# rev18.net
KiCad netlist of a schematic drawn in EAGLE
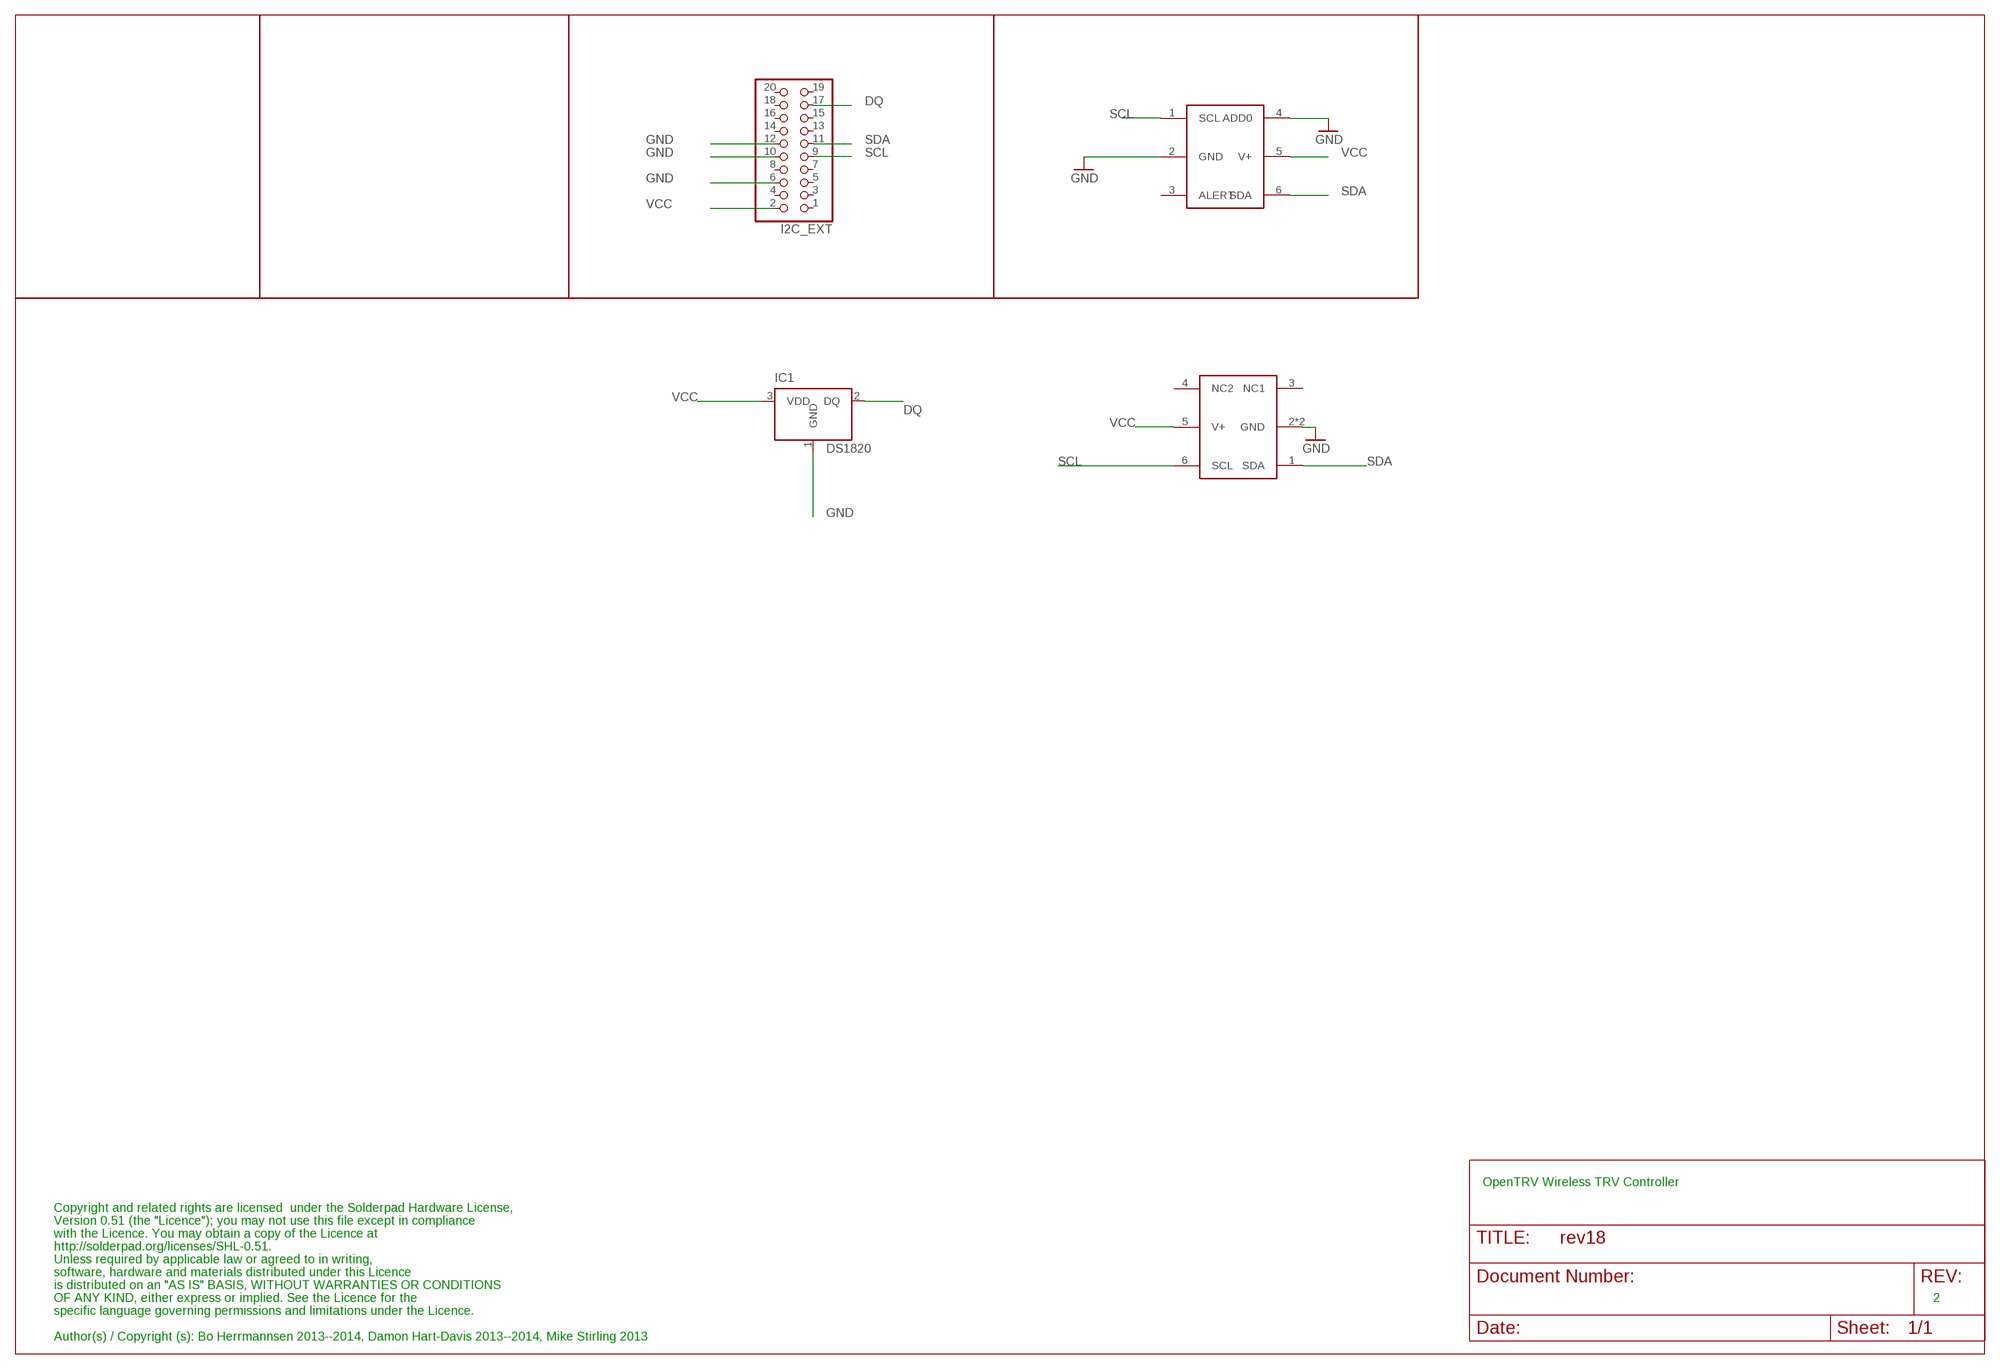
[diagram p0: schematic, sheet 1]

(export (version "E")
  (design (tool "Eeschema 10.0.6"))
  (components
    (comp (ref "I2C_EXT")
      (value "PINHD-2X10")
      (footprint "eagle-import:2X10")
      (libsource (lib "eagle-import") (part "PINHD-2X10"))
    )
    (comp (ref "IC1")
      (value "DS1820")
      (footprint "eagle-import:TO-92")
      (libsource (lib "eagle-import") (part "DS1820"))
    )
    (comp (ref "TMP112")
      (value "TMP1")
      (footprint "eagle-import:TMP112")
      (libsource (lib "eagle-import") (part "TMP112"))
    )
    (comp (ref "U$4")
      (value "SHT21")
      (footprint "eagle-import:SHT21")
      (libsource (lib "eagle-import") (part "SHT21"))
    )
  )
  (nets
    (net (code "1") (name "/DQ") (class "Default")
      (node (ref "I2C_EXT") (pin "17") (pinfunction "17_17") (pintype "passive"))
      (node (ref "IC1") (pin "2") (pinfunction "DQ_2") (pintype "output"))
    )
    (net (code "2") (name "/SCL") (class "Default")
      (node (ref "I2C_EXT") (pin "9") (pinfunction "9_9") (pintype "passive"))
      (node (ref "TMP112") (pin "1") (pinfunction "SCL_1") (pintype "bidirectional"))
      (node (ref "U$4") (pin "6") (pinfunction "SCL_6") (pintype "bidirectional"))
    )
    (net (code "3") (name "/SDA") (class "Default")
      (node (ref "I2C_EXT") (pin "11") (pinfunction "11_11") (pintype "passive"))
      (node (ref "TMP112") (pin "6") (pinfunction "SDA_6") (pintype "bidirectional"))
      (node (ref "U$4") (pin "1") (pinfunction "SDA_1") (pintype "bidirectional"))
    )
    (net (code "4") (name "/VCC") (class "Default")
      (node (ref "I2C_EXT") (pin "2") (pinfunction "2_2") (pintype "passive"))
      (node (ref "IC1") (pin "3") (pinfunction "VDD_3") (pintype "input"))
      (node (ref "TMP112") (pin "5") (pinfunction "V+_5") (pintype "bidirectional"))
      (node (ref "U$4") (pin "5") (pinfunction "V+_5") (pintype "bidirectional"))
    )
    (net (code "5") (name "GND") (class "Default")
      (node (ref "I2C_EXT") (pin "10") (pinfunction "10_10") (pintype "passive"))
      (node (ref "I2C_EXT") (pin "12") (pinfunction "12_12") (pintype "passive"))
      (node (ref "I2C_EXT") (pin "6") (pinfunction "6_6") (pintype "passive"))
      (node (ref "IC1") (pin "1") (pinfunction "GND_1") (pintype "power_in"))
      (node (ref "TMP112") (pin "2") (pinfunction "GND_2") (pintype "bidirectional"))
      (node (ref "TMP112") (pin "4") (pinfunction "ADD0_4") (pintype "bidirectional"))
      (node (ref "U$4") (pin "2") (pinfunction "GND_2") (pintype "bidirectional"))
      (node (ref "U$4") (pin "P$1") (pinfunction "GND_P$1") (pintype "bidirectional"))
    )
    (net (code "6") (name "unconnected-(I2C_EXT-Pad1)") (class "Default")
      (node (ref "I2C_EXT") (pin "1") (pinfunction "1_1") (pintype "passive"))
    )
    (net (code "7") (name "unconnected-(I2C_EXT-Pad3)") (class "Default")
      (node (ref "I2C_EXT") (pin "3") (pinfunction "3_3") (pintype "passive"))
    )
    (net (code "8") (name "unconnected-(I2C_EXT-Pad4)") (class "Default")
      (node (ref "I2C_EXT") (pin "4") (pinfunction "4_4") (pintype "passive"))
    )
    (net (code "9") (name "unconnected-(I2C_EXT-Pad5)") (class "Default")
      (node (ref "I2C_EXT") (pin "5") (pinfunction "5_5") (pintype "passive"))
    )
    (net (code "10") (name "unconnected-(I2C_EXT-Pad7)") (class "Default")
      (node (ref "I2C_EXT") (pin "7") (pinfunction "7_7") (pintype "passive"))
    )
    (net (code "11") (name "unconnected-(I2C_EXT-Pad8)") (class "Default")
      (node (ref "I2C_EXT") (pin "8") (pinfunction "8_8") (pintype "passive"))
    )
    (net (code "12") (name "unconnected-(I2C_EXT-Pad13)") (class "Default")
      (node (ref "I2C_EXT") (pin "13") (pinfunction "13_13") (pintype "passive"))
    )
    (net (code "13") (name "unconnected-(I2C_EXT-Pad14)") (class "Default")
      (node (ref "I2C_EXT") (pin "14") (pinfunction "14_14") (pintype "passive"))
    )
    (net (code "14") (name "unconnected-(I2C_EXT-Pad15)") (class "Default")
      (node (ref "I2C_EXT") (pin "15") (pinfunction "15_15") (pintype "passive"))
    )
    (net (code "15") (name "unconnected-(I2C_EXT-Pad16)") (class "Default")
      (node (ref "I2C_EXT") (pin "16") (pinfunction "16_16") (pintype "passive"))
    )
    (net (code "16") (name "unconnected-(I2C_EXT-Pad18)") (class "Default")
      (node (ref "I2C_EXT") (pin "18") (pinfunction "18_18") (pintype "passive"))
    )
    (net (code "17") (name "unconnected-(I2C_EXT-Pad19)") (class "Default")
      (node (ref "I2C_EXT") (pin "19") (pinfunction "19_19") (pintype "passive"))
    )
    (net (code "18") (name "unconnected-(I2C_EXT-Pad20)") (class "Default")
      (node (ref "I2C_EXT") (pin "20") (pinfunction "20_20") (pintype "passive"))
    )
    (net (code "19") (name "unconnected-(TMP112-ALERT-Pad3)") (class "Default")
      (node (ref "TMP112") (pin "3") (pinfunction "ALERT_3") (pintype "bidirectional"))
    )
    (net (code "20") (name "unconnected-(U$4-NC1-Pad3)") (class "Default")
      (node (ref "U$4") (pin "3") (pinfunction "NC1_3") (pintype "bidirectional"))
    )
    (net (code "21") (name "unconnected-(U$4-NC2-Pad4)") (class "Default")
      (node (ref "U$4") (pin "4") (pinfunction "NC2_4") (pintype "bidirectional"))
    )
  )
)
